# BARRERA.net
KiCad netlist of a schematic drawn in EAGLE
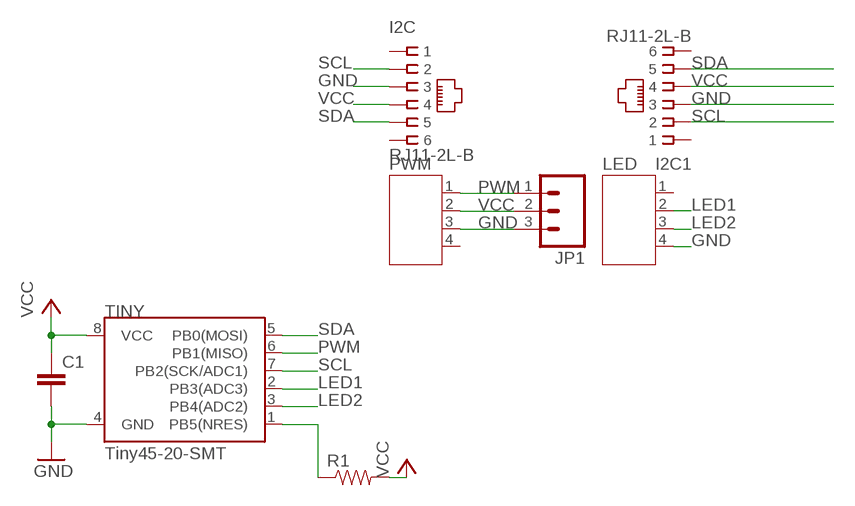
[diagram p0: schematic, sheet 1]

(export (version "E")
  (design (tool "Eeschema 10.0.6"))
  (components
    (comp (ref "C1")
      (value "CAP0603-CAP")
      (footprint "eagle-import:0603-CAP")
      (libsource (lib "eagle-import") (part "CAP0603-CAP"))
    )
    (comp (ref "I2C")
      (value "RJ11-2L-B")
      (footprint "eagle-import:RJ11-NO_SHIELD")
      (fields (field (name "MF") "TYCO ELECTRONICS"))
      (libsource (lib "eagle-import") (part "RJ11-2L-B"))
    )
    (comp (ref "I2C1")
      (value "RJ11-2L-B")
      (footprint "eagle-import:RJ11-NO_SHIELD")
      (fields (field (name "MF") "TYCO ELECTRONICS"))
      (libsource (lib "eagle-import") (part "RJ11-2L-B"))
    )
    (comp (ref "JP1")
      (value "M03PTH")
      (footprint "eagle-import:1X03")
      (libsource (lib "eagle-import") (part "M03PTH"))
    )
    (comp (ref "LED")
      (value "JST-PH4")
      (footprint "eagle-import:JST-PH4")
      (libsource (lib "eagle-import") (part "JST-PH4"))
    )
    (comp (ref "PWM")
      (value "JST-PH4")
      (footprint "eagle-import:JST-PH4")
      (libsource (lib "eagle-import") (part "JST-PH4"))
    )
    (comp (ref "R1")
      (value "RESISTOR0603")
      (footprint "eagle-import:0603-RES")
      (libsource (lib "eagle-import") (part "RESISTOR0603"))
    )
    (comp (ref "TINY")
      (value "Tiny45-20-SMT")
      (footprint "eagle-import:SO08-EIAJ")
      (libsource (lib "eagle-import") (part "ATTINY45TINY45-20-SMT"))
    )
  )
  (nets
    (net (code "1") (name "/LED1") (class "Default")
      (node (ref "LED") (pin "2") (pinfunction "2_2") (pintype "passive"))
      (node (ref "TINY") (pin "2") (pinfunction "PB3(ADC3)_2") (pintype "bidirectional"))
    )
    (net (code "2") (name "/LED2") (class "Default")
      (node (ref "LED") (pin "3") (pinfunction "3_3") (pintype "passive"))
      (node (ref "TINY") (pin "3") (pinfunction "PB4(ADC2)_3") (pintype "bidirectional"))
    )
    (net (code "3") (name "/PWM") (class "Default")
      (node (ref "JP1") (pin "1") (pinfunction "1_1") (pintype "passive"))
      (node (ref "PWM") (pin "1") (pinfunction "1_1") (pintype "passive"))
      (node (ref "TINY") (pin "6") (pinfunction "PB1(MISO)_6") (pintype "bidirectional"))
    )
    (net (code "4") (name "/SCL") (class "Default")
      (node (ref "I2C") (pin "2") (pinfunction "2_2") (pintype "passive"))
      (node (ref "I2C1") (pin "2") (pinfunction "2_2") (pintype "passive"))
      (node (ref "TINY") (pin "7") (pinfunction "PB2(SCK/ADC1)_7") (pintype "bidirectional"))
    )
    (net (code "5") (name "/SDA") (class "Default")
      (node (ref "I2C") (pin "5") (pinfunction "5_5") (pintype "passive"))
      (node (ref "I2C1") (pin "5") (pinfunction "5_5") (pintype "passive"))
      (node (ref "TINY") (pin "5") (pinfunction "PB0(MOSI)_5") (pintype "bidirectional"))
    )
    (net (code "6") (name "GND") (class "Default")
      (node (ref "C1") (pin "2") (pinfunction "2_2") (pintype "passive"))
      (node (ref "I2C") (pin "3") (pinfunction "3_3") (pintype "passive"))
      (node (ref "I2C1") (pin "3") (pinfunction "3_3") (pintype "passive"))
      (node (ref "JP1") (pin "3") (pinfunction "3_3") (pintype "passive"))
      (node (ref "LED") (pin "4") (pinfunction "4_4") (pintype "passive"))
      (node (ref "PWM") (pin "3") (pinfunction "3_3") (pintype "passive"))
      (node (ref "TINY") (pin "4") (pinfunction "GND_4") (pintype "bidirectional"))
    )
    (net (code "7") (name "Net-(TINY-PB5(NRES))") (class "Default")
      (node (ref "R1") (pin "1") (pinfunction "1_1") (pintype "passive"))
      (node (ref "TINY") (pin "1") (pinfunction "PB5(NRES)_1") (pintype "bidirectional"))
    )
    (net (code "8") (name "VCC") (class "Default")
      (node (ref "C1") (pin "1") (pinfunction "1_1") (pintype "passive"))
      (node (ref "I2C") (pin "4") (pinfunction "4_4") (pintype "passive"))
      (node (ref "I2C1") (pin "4") (pinfunction "4_4") (pintype "passive"))
      (node (ref "JP1") (pin "2") (pinfunction "2_2") (pintype "passive"))
      (node (ref "PWM") (pin "2") (pinfunction "2_2") (pintype "passive"))
      (node (ref "R1") (pin "2") (pinfunction "2_2") (pintype "passive"))
      (node (ref "TINY") (pin "8") (pinfunction "VCC_8") (pintype "bidirectional"))
    )
    (net (code "9") (name "unconnected-(I2C-Pad1)") (class "Default")
      (node (ref "I2C") (pin "1") (pinfunction "1_1") (pintype "passive"))
    )
    (net (code "10") (name "unconnected-(I2C-Pad6)") (class "Default")
      (node (ref "I2C") (pin "6") (pinfunction "6_6") (pintype "passive"))
    )
    (net (code "11") (name "unconnected-(I2C1-Pad1)") (class "Default")
      (node (ref "I2C1") (pin "1") (pinfunction "1_1") (pintype "passive"))
    )
    (net (code "12") (name "unconnected-(I2C1-Pad6)") (class "Default")
      (node (ref "I2C1") (pin "6") (pinfunction "6_6") (pintype "passive"))
    )
    (net (code "13") (name "unconnected-(LED-Pad1)") (class "Default")
      (node (ref "LED") (pin "1") (pinfunction "1_1") (pintype "passive"))
    )
    (net (code "14") (name "unconnected-(PWM-Pad4)") (class "Default")
      (node (ref "PWM") (pin "4") (pinfunction "4_4") (pintype "passive"))
    )
  )
)
